# InputAmplifier.net
KiCad netlist of a schematic drawn in Altium Designer
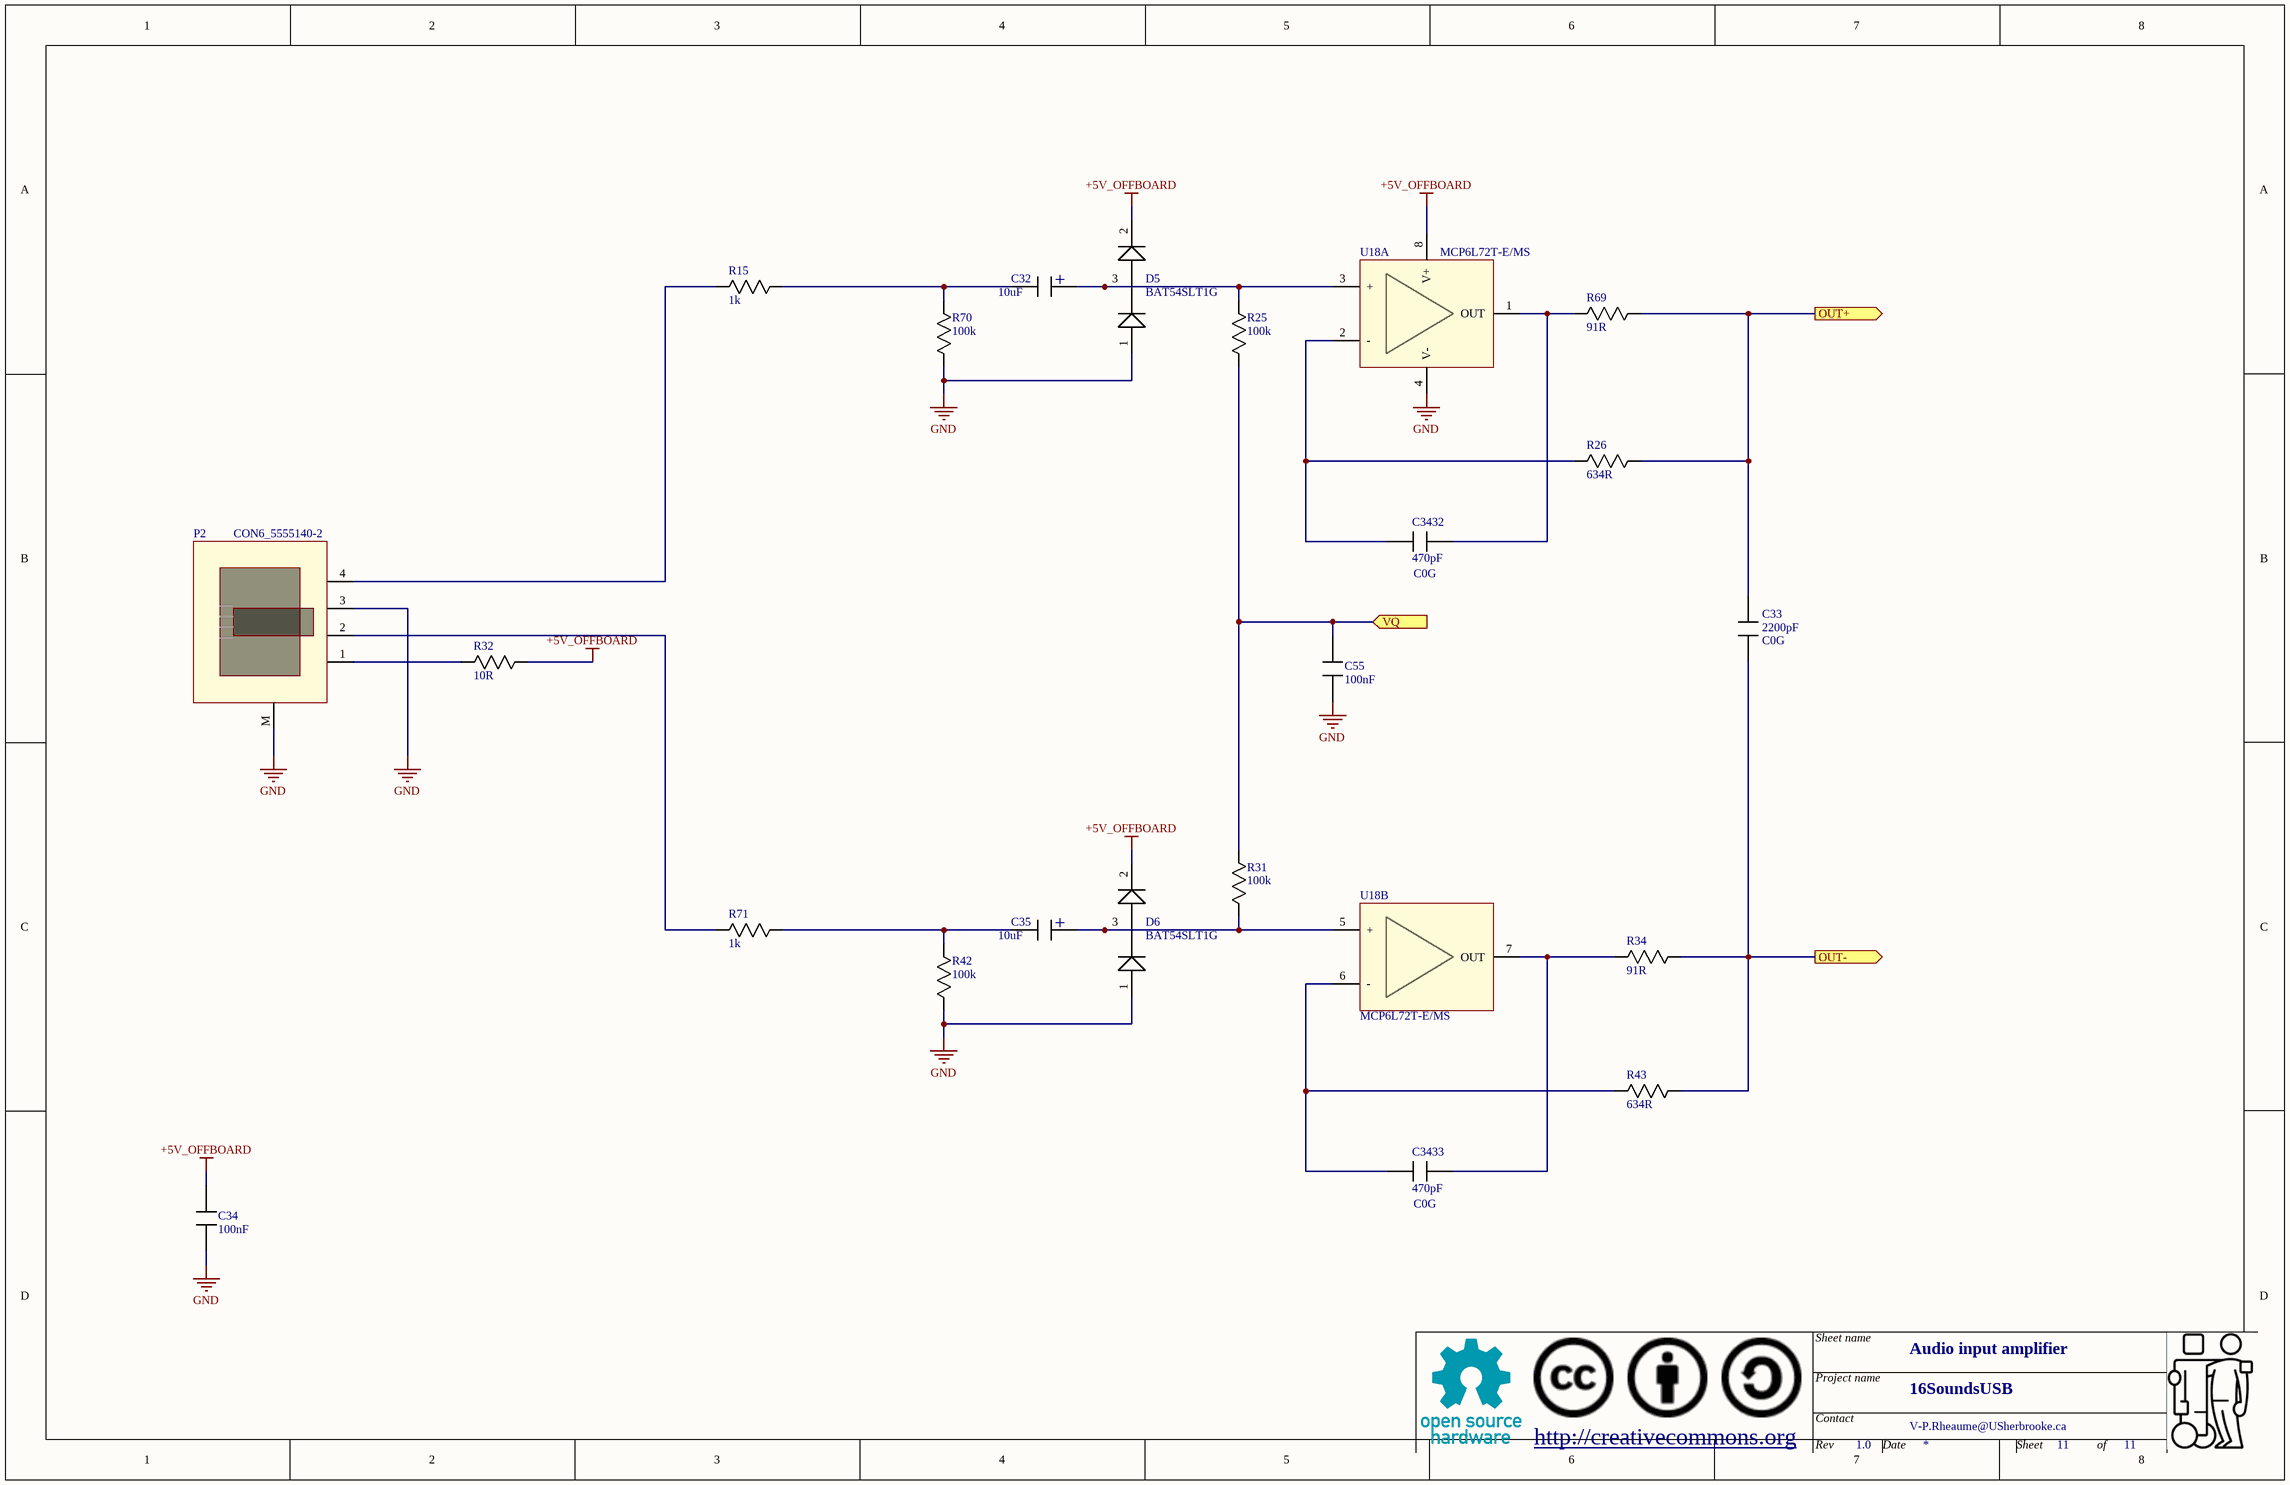
[diagram p0: InputAmplifier.SchDoc]

(export (version "E")
  (design (tool "Eeschema 10.0.6"))
  (components
    (comp (ref "C32")
      (value "10uF")
      (footprint "CAP_RAD_SMD_DIA157")
      (description "Capacitor")
      (fields (field (name "Comment") "Capacitor_Polarized"))
      (libsource (lib "INTER_2014") (part "Capacitor_Polarized"))
    )
    (comp (ref "C33")
      (value "2200pF")
      (footprint "0603")
      (description "Capacitor")
      (fields (field (name "TYPE") "C0G"))
      (libsource (lib "INTER_2014") (part "Capacitor"))
    )
    (comp (ref "C34")
      (value "100nF")
      (footprint "0603")
      (description "Capacitor")
      (libsource (lib "INTER_2014") (part "Capacitor"))
    )
    (comp (ref "C35")
      (value "10uF")
      (footprint "CAP_RAD_SMD_DIA157")
      (description "Capacitor")
      (fields (field (name "Comment") "Capacitor_Polarized"))
      (libsource (lib "INTER_2014") (part "Capacitor_Polarized"))
    )
    (comp (ref "C55")
      (value "100nF")
      (footprint "0603")
      (description "Capacitor")
      (libsource (lib "INTER_2014") (part "Capacitor"))
    )
    (comp (ref "C3432")
      (value "470pF")
      (footprint "0603")
      (description "Capacitor")
      (fields (field (name "TYPE") "C0G"))
      (libsource (lib "INTER_2014") (part "Capacitor"))
    )
    (comp (ref "C3433")
      (value "470pF")
      (footprint "0603")
      (description "Capacitor")
      (fields (field (name "TYPE") "C0G"))
      (libsource (lib "INTER_2014") (part "Capacitor"))
    )
    (comp (ref "D5")
      (value "Diode_dual")
      (footprint "SOT23_132")
      (description "Diode")
      (fields (field (name "MFG") "Onsemi") (field (name "MFG_PN") "BAT54SLT1G"))
      (libsource (lib "INTER_2014") (part "Diode_dual"))
    )
    (comp (ref "D6")
      (value "Diode_dual")
      (footprint "SOT23_132")
      (description "Diode")
      (fields (field (name "MFG") "Onsemi") (field (name "MFG_PN") "BAT54SLT1G"))
      (libsource (lib "INTER_2014") (part "Diode_dual"))
    )
    (comp (ref "P2")
      (value "CON6_5555140-2")
      (footprint "CONN4_5555140-2")
      (description "6p4c RJ11/RJ14, shielded (5555165-2 unshielded)")
      (fields (field (name "MFG") "TE"))
      (libsource (lib "INTER_2014") (part "CON6_5555140-2"))
    )
    (comp (ref "R15")
      (value "1k")
      (footprint "0603")
      (description "Resistor")
      (libsource (lib "INTER_2014") (part "Resistor"))
    )
    (comp (ref "R25")
      (value "100k")
      (footprint "0603")
      (description "Resistor")
      (libsource (lib "INTER_2014") (part "Resistor"))
    )
    (comp (ref "R26")
      (value "634R")
      (footprint "0603")
      (description "Resistor")
      (libsource (lib "INTER_2014") (part "Resistor"))
    )
    (comp (ref "R31")
      (value "100k")
      (footprint "0603")
      (description "Resistor")
      (libsource (lib "INTER_2014") (part "Resistor"))
    )
    (comp (ref "R32")
      (value "10R")
      (footprint "0603")
      (description "Resistor")
      (libsource (lib "INTER_2014") (part "Resistor"))
    )
    (comp (ref "R34")
      (value "91R")
      (footprint "0603")
      (description "Resistor")
      (libsource (lib "INTER_2014") (part "Resistor"))
    )
    (comp (ref "R42")
      (value "100k")
      (footprint "0603")
      (description "Resistor")
      (libsource (lib "INTER_2014") (part "Resistor"))
    )
    (comp (ref "R43")
      (value "634R")
      (footprint "0603")
      (description "Resistor")
      (libsource (lib "INTER_2014") (part "Resistor"))
    )
    (comp (ref "R69")
      (value "91R")
      (footprint "0603")
      (description "Resistor")
      (libsource (lib "INTER_2014") (part "Resistor"))
    )
    (comp (ref "R70")
      (value "100k")
      (footprint "0603")
      (description "Resistor")
      (libsource (lib "INTER_2014") (part "Resistor"))
    )
    (comp (ref "R71")
      (value "1k")
      (footprint "0603")
      (description "Resistor")
      (libsource (lib "INTER_2014") (part "Resistor"))
    )
    (comp (ref "U18")
      (value "OPA_DUAL")
      (footprint "SOP127P600-8N")
      (description "Dual amplifier (standard)")
      (fields (field (name "MFG") "Microchip") (field (name "MFG_PN") "MCP6L72T-E/MS"))
      (libsource (lib "INTER_2014") (part "OPA_DUAL"))
    )
  )
  (nets
    (net (code "1") (name "+5V_OFFBOARD") (class "Default")
      (node (ref "C34") (pin "1") (pintype "passive"))
      (node (ref "D5") (pin "2") (pinfunction "K_2") (pintype "passive"))
      (node (ref "D6") (pin "2") (pinfunction "K_2") (pintype "passive"))
      (node (ref "R32") (pin "2") (pintype "passive"))
      (node (ref "U18") (pin "8") (pinfunction "V+_8") (pintype "passive"))
    )
    (net (code "2") (name "/OUT+") (class "Default")
      (node (ref "C33") (pin "1") (pintype "passive"))
      (node (ref "R26") (pin "2") (pintype "passive"))
      (node (ref "R69") (pin "2") (pintype "passive"))
    )
    (net (code "3") (name "/OUT-") (class "Default")
      (node (ref "C33") (pin "2") (pintype "passive"))
      (node (ref "R34") (pin "2") (pintype "passive"))
      (node (ref "R43") (pin "2") (pintype "passive"))
    )
    (net (code "4") (name "/VQ") (class "Default")
      (node (ref "C55") (pin "1") (pintype "passive"))
      (node (ref "R25") (pin "1") (pintype "passive"))
      (node (ref "R31") (pin "2") (pintype "passive"))
    )
    (net (code "5") (name "GND") (class "Default")
      (node (ref "C34") (pin "2") (pintype "passive"))
      (node (ref "C55") (pin "2") (pintype "passive"))
      (node (ref "D5") (pin "1") (pinfunction "K_1") (pintype "passive"))
      (node (ref "D6") (pin "1") (pinfunction "K_1") (pintype "passive"))
      (node (ref "P2") (pin "3") (pintype "passive"))
      (node (ref "P2") (pin "M") (pintype "passive"))
      (node (ref "R42") (pin "1") (pintype "passive"))
      (node (ref "R70") (pin "1") (pintype "passive"))
      (node (ref "U18") (pin "4") (pinfunction "V-_4") (pintype "passive"))
    )
    (net (code "6") (name "Net-(C32-Pad-)") (class "Default")
      (node (ref "C32") (pin "-") (pintype "passive"))
      (node (ref "R15") (pin "2") (pintype "passive"))
      (node (ref "R70") (pin "2") (pintype "passive"))
    )
    (net (code "7") (name "Net-(C35-Pad-)") (class "Default")
      (node (ref "C35") (pin "-") (pintype "passive"))
      (node (ref "R42") (pin "2") (pintype "passive"))
      (node (ref "R71") (pin "2") (pintype "passive"))
    )
    (net (code "8") (name "Net-(D5-AK)") (class "Default")
      (node (ref "C32") (pin "+") (pintype "passive"))
      (node (ref "D5") (pin "3") (pinfunction "AK_3") (pintype "passive"))
      (node (ref "R25") (pin "2") (pintype "passive"))
      (node (ref "U18") (pin "3") (pinfunction "+_3") (pintype "passive"))
    )
    (net (code "9") (name "Net-(D6-AK)") (class "Default")
      (node (ref "C35") (pin "+") (pintype "passive"))
      (node (ref "D6") (pin "3") (pinfunction "AK_3") (pintype "passive"))
      (node (ref "R31") (pin "1") (pintype "passive"))
      (node (ref "U18") (pin "5") (pinfunction "+_5") (pintype "passive"))
    )
    (net (code "10") (name "Net-(P2-Pad1)") (class "Default")
      (node (ref "P2") (pin "1") (pintype "passive"))
      (node (ref "R32") (pin "1") (pintype "passive"))
    )
    (net (code "11") (name "Net-(P2-Pad2)") (class "Default")
      (node (ref "P2") (pin "2") (pintype "passive"))
      (node (ref "R71") (pin "1") (pintype "passive"))
    )
    (net (code "12") (name "Net-(P2-Pad4)") (class "Default")
      (node (ref "P2") (pin "4") (pintype "passive"))
      (node (ref "R15") (pin "1") (pintype "passive"))
    )
    (net (code "13") (name "Net-(U18A--)") (class "Default")
      (node (ref "C3432") (pin "1") (pintype "passive"))
      (node (ref "R26") (pin "1") (pintype "passive"))
      (node (ref "U18") (pin "2") (pinfunction "-_2") (pintype "passive"))
    )
    (net (code "14") (name "Net-(U18A-OUT)") (class "Default")
      (node (ref "C3432") (pin "2") (pintype "passive"))
      (node (ref "R69") (pin "1") (pintype "passive"))
      (node (ref "U18") (pin "1") (pinfunction "OUT_1") (pintype "passive"))
    )
    (net (code "15") (name "Net-(U18B--)") (class "Default")
      (node (ref "C3433") (pin "1") (pintype "passive"))
      (node (ref "R43") (pin "1") (pintype "passive"))
      (node (ref "U18") (pin "6") (pinfunction "-_6") (pintype "passive"))
    )
    (net (code "16") (name "Net-(U18B-OUT)") (class "Default")
      (node (ref "C3433") (pin "2") (pintype "passive"))
      (node (ref "R34") (pin "1") (pintype "passive"))
      (node (ref "U18") (pin "7") (pinfunction "OUT_7") (pintype "passive"))
    )
  )
)
